# CF_DAC_FILTER.net
KiCad netlist of a schematic drawn in Altium Designer
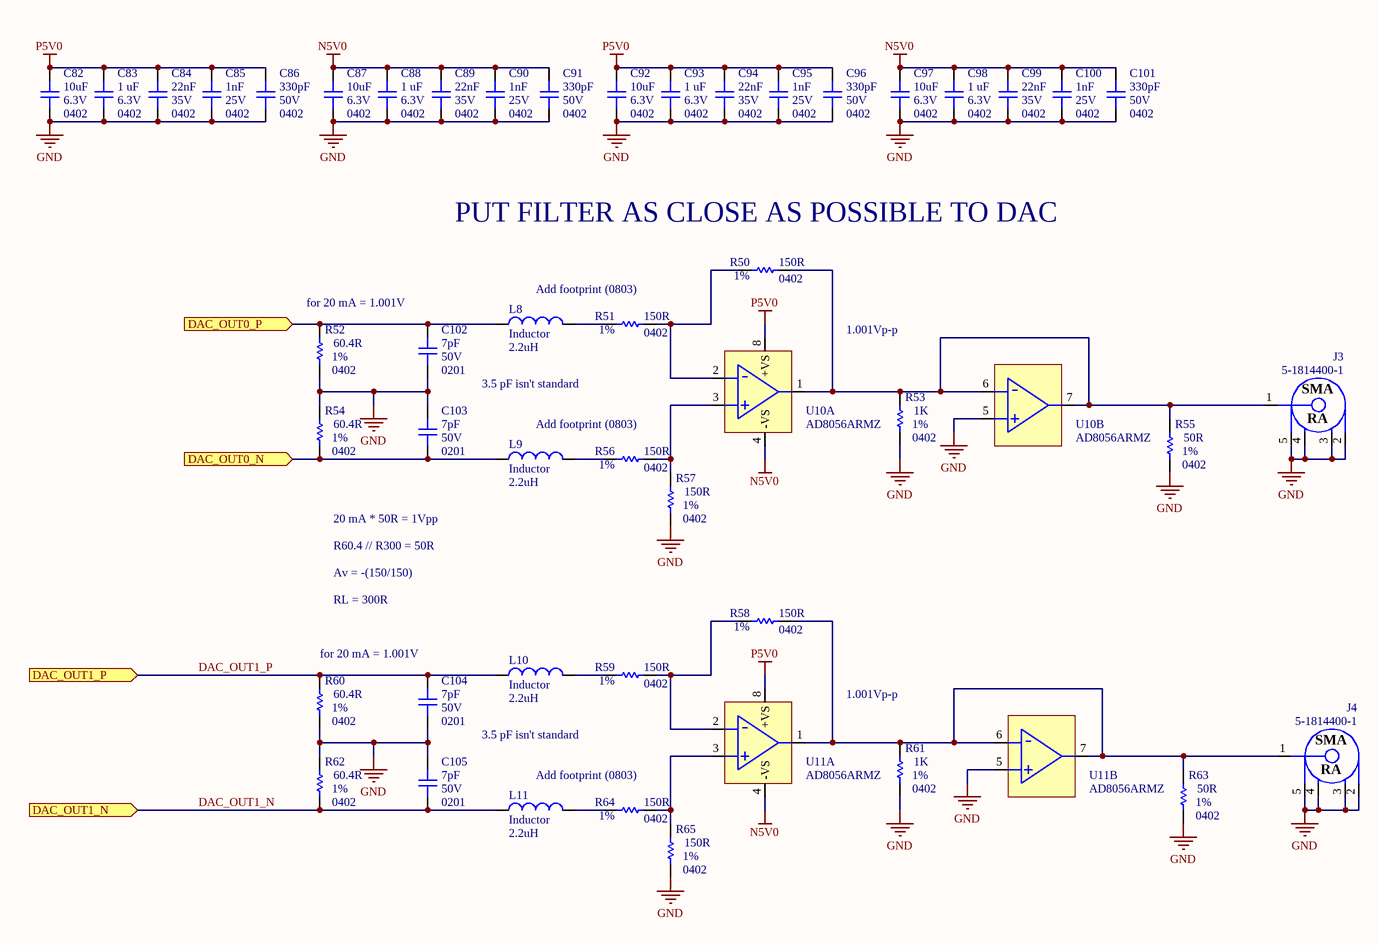
[diagram p0: CF_DAC_FILTER.SchDoc]

(export (version "E")
  (design (tool "Eeschema 10.0.6"))
  (components
    (comp (ref "C82")
      (value "10uF")
      (footprint "CAP_0402")
      (description "CAP - 0402")
      (fields
        (field (name "VOLTAGE") "6.3V")
        (field (name "PACKAGE") "0402")
        (field (name "CREATEDBY") "Jonathan Bouchard")
      )
      (libsource (lib "S7CAS_Lib2019_REV1_00") (part "CAP - 0402"))
    )
    (comp (ref "C83")
      (value "1 uF")
      (footprint "CAP_0402")
      (description "CAP - 0402")
      (fields
        (field (name "VOLTAGE") "6.3V")
        (field (name "PACKAGE") "0402")
        (field (name "CREATEDBY") "Jonathan Bouchard")
      )
      (libsource (lib "S7CAS_Lib2019_REV1_00") (part "CAP - 0402"))
    )
    (comp (ref "C84")
      (value "22nF")
      (footprint "CAP_0402")
      (description "CAP - 0402")
      (fields
        (field (name "VOLTAGE") "35V")
        (field (name "PACKAGE") "0402")
        (field (name "CREATEDBY") "Jonathan Bouchard")
      )
      (libsource (lib "S7CAS_Lib2019_REV1_00") (part "CAP - 0402"))
    )
    (comp (ref "C85")
      (value "1nF")
      (footprint "CAP_0402")
      (description "CAP - 0402")
      (fields
        (field (name "VOLTAGE") "25V")
        (field (name "PACKAGE") "0402")
        (field (name "CREATEDBY") "Jonathan Bouchard")
      )
      (libsource (lib "S7CAS_Lib2019_REV1_00") (part "CAP - 0402"))
    )
    (comp (ref "C86")
      (value "330pF")
      (footprint "CAP_0402")
      (description "CAP - 0402")
      (fields
        (field (name "VOLTAGE") "50V")
        (field (name "PACKAGE") "0402")
        (field (name "CREATEDBY") "Jonathan Bouchard")
      )
      (libsource (lib "S7CAS_Lib2019_REV1_00") (part "CAP - 0402"))
    )
    (comp (ref "C87")
      (value "10uF")
      (footprint "CAP_0402")
      (description "CAP - 0402")
      (fields
        (field (name "VOLTAGE") "6.3V")
        (field (name "PACKAGE") "0402")
        (field (name "CREATEDBY") "Jonathan Bouchard")
      )
      (libsource (lib "S7CAS_Lib2019_REV1_00") (part "CAP - 0402"))
    )
    (comp (ref "C88")
      (value "1 uF")
      (footprint "CAP_0402")
      (description "CAP - 0402")
      (fields
        (field (name "VOLTAGE") "6.3V")
        (field (name "PACKAGE") "0402")
        (field (name "CREATEDBY") "Jonathan Bouchard")
      )
      (libsource (lib "S7CAS_Lib2019_REV1_00") (part "CAP - 0402"))
    )
    (comp (ref "C89")
      (value "22nF")
      (footprint "CAP_0402")
      (description "CAP - 0402")
      (fields
        (field (name "VOLTAGE") "35V")
        (field (name "PACKAGE") "0402")
        (field (name "CREATEDBY") "Jonathan Bouchard")
      )
      (libsource (lib "S7CAS_Lib2019_REV1_00") (part "CAP - 0402"))
    )
    (comp (ref "C90")
      (value "1nF")
      (footprint "CAP_0402")
      (description "CAP - 0402")
      (fields
        (field (name "VOLTAGE") "25V")
        (field (name "PACKAGE") "0402")
        (field (name "CREATEDBY") "Jonathan Bouchard")
      )
      (libsource (lib "S7CAS_Lib2019_REV1_00") (part "CAP - 0402"))
    )
    (comp (ref "C91")
      (value "330pF")
      (footprint "CAP_0402")
      (description "CAP - 0402")
      (fields
        (field (name "VOLTAGE") "50V")
        (field (name "PACKAGE") "0402")
        (field (name "CREATEDBY") "Jonathan Bouchard")
      )
      (libsource (lib "S7CAS_Lib2019_REV1_00") (part "CAP - 0402"))
    )
    (comp (ref "C92")
      (value "10uF")
      (footprint "CAP_0402")
      (description "CAP - 0402")
      (fields
        (field (name "VOLTAGE") "6.3V")
        (field (name "PACKAGE") "0402")
        (field (name "CREATEDBY") "Jonathan Bouchard")
      )
      (libsource (lib "S7CAS_Lib2019_REV1_00") (part "CAP - 0402"))
    )
    (comp (ref "C93")
      (value "1 uF")
      (footprint "CAP_0402")
      (description "CAP - 0402")
      (fields
        (field (name "VOLTAGE") "6.3V")
        (field (name "PACKAGE") "0402")
        (field (name "CREATEDBY") "Jonathan Bouchard")
      )
      (libsource (lib "S7CAS_Lib2019_REV1_00") (part "CAP - 0402"))
    )
    (comp (ref "C94")
      (value "22nF")
      (footprint "CAP_0402")
      (description "CAP - 0402")
      (fields
        (field (name "VOLTAGE") "35V")
        (field (name "PACKAGE") "0402")
        (field (name "CREATEDBY") "Jonathan Bouchard")
      )
      (libsource (lib "S7CAS_Lib2019_REV1_00") (part "CAP - 0402"))
    )
    (comp (ref "C95")
      (value "1nF")
      (footprint "CAP_0402")
      (description "CAP - 0402")
      (fields
        (field (name "VOLTAGE") "25V")
        (field (name "PACKAGE") "0402")
        (field (name "CREATEDBY") "Jonathan Bouchard")
      )
      (libsource (lib "S7CAS_Lib2019_REV1_00") (part "CAP - 0402"))
    )
    (comp (ref "C96")
      (value "330pF")
      (footprint "CAP_0402")
      (description "CAP - 0402")
      (fields
        (field (name "VOLTAGE") "50V")
        (field (name "PACKAGE") "0402")
        (field (name "CREATEDBY") "Jonathan Bouchard")
      )
      (libsource (lib "S7CAS_Lib2019_REV1_00") (part "CAP - 0402"))
    )
    (comp (ref "C97")
      (value "10uF")
      (footprint "CAP_0402")
      (description "CAP - 0402")
      (fields
        (field (name "VOLTAGE") "6.3V")
        (field (name "PACKAGE") "0402")
        (field (name "CREATEDBY") "Jonathan Bouchard")
      )
      (libsource (lib "S7CAS_Lib2019_REV1_00") (part "CAP - 0402"))
    )
    (comp (ref "C98")
      (value "1 uF")
      (footprint "CAP_0402")
      (description "CAP - 0402")
      (fields
        (field (name "VOLTAGE") "6.3V")
        (field (name "PACKAGE") "0402")
        (field (name "CREATEDBY") "Jonathan Bouchard")
      )
      (libsource (lib "S7CAS_Lib2019_REV1_00") (part "CAP - 0402"))
    )
    (comp (ref "C99")
      (value "22nF")
      (footprint "CAP_0402")
      (description "CAP - 0402")
      (fields
        (field (name "VOLTAGE") "35V")
        (field (name "PACKAGE") "0402")
        (field (name "CREATEDBY") "Jonathan Bouchard")
      )
      (libsource (lib "S7CAS_Lib2019_REV1_00") (part "CAP - 0402"))
    )
    (comp (ref "C100")
      (value "1nF")
      (footprint "CAP_0402")
      (description "CAP - 0402")
      (fields
        (field (name "VOLTAGE") "25V")
        (field (name "PACKAGE") "0402")
        (field (name "CREATEDBY") "Jonathan Bouchard")
      )
      (libsource (lib "S7CAS_Lib2019_REV1_00") (part "CAP - 0402"))
    )
    (comp (ref "C101")
      (value "330pF")
      (footprint "CAP_0402")
      (description "CAP - 0402")
      (fields
        (field (name "VOLTAGE") "50V")
        (field (name "PACKAGE") "0402")
        (field (name "CREATEDBY") "Jonathan Bouchard")
      )
      (libsource (lib "S7CAS_Lib2019_REV1_00") (part "CAP - 0402"))
    )
    (comp (ref "C102")
      (value "7pF")
      (footprint "CAP_0201")
      (description "CAP - 0201")
      (fields
        (field (name "VOLTAGE") "50V")
        (field (name "PACKAGE") "0201")
        (field (name "CREATEDBY") "Jonathan Bouchard")
      )
      (libsource (lib "S7CAS_Lib2019_REV1_00") (part "CAP - 0201"))
    )
    (comp (ref "C103")
      (value "7pF")
      (footprint "CAP_0201")
      (description "CAP - 0201")
      (fields
        (field (name "VOLTAGE") "50V")
        (field (name "PACKAGE") "0201")
        (field (name "CREATEDBY") "Jonathan Bouchard")
      )
      (libsource (lib "S7CAS_Lib2019_REV1_00") (part "CAP - 0201"))
    )
    (comp (ref "C104")
      (value "7pF")
      (footprint "CAP_0201")
      (description "CAP - 0201")
      (fields
        (field (name "VOLTAGE") "50V")
        (field (name "PACKAGE") "0201")
        (field (name "CREATEDBY") "Jonathan Bouchard")
      )
      (libsource (lib "S7CAS_Lib2019_REV1_00") (part "CAP - 0201"))
    )
    (comp (ref "C105")
      (value "7pF")
      (footprint "CAP_0201")
      (description "CAP - 0201")
      (fields
        (field (name "VOLTAGE") "50V")
        (field (name "PACKAGE") "0201")
        (field (name "CREATEDBY") "Jonathan Bouchard")
      )
      (libsource (lib "S7CAS_Lib2019_REV1_00") (part "CAP - 0201"))
    )
    (comp (ref "J3")
      (value "5-1814400-1")
      (footprint "CONN_SMA_5-1814400-1")
      (description "CONN -  SMA JACK R/A 50 OHM - TH")
      (fields
        (field (name "MFG") "TE Connectivity AMP Connectors")
        (field (name "CREATEDBY") "Jonathan Bouchard")
      )
      (libsource (lib "S7CAS_Lib2019_REV1_00") (part "CONN_SMA_5-1814400-1"))
    )
    (comp (ref "J4")
      (value "5-1814400-1")
      (footprint "CONN_SMA_5-1814400-1")
      (description "CONN -  SMA JACK R/A 50 OHM - TH")
      (fields
        (field (name "MFG") "TE Connectivity AMP Connectors")
        (field (name "CREATEDBY") "Jonathan Bouchard")
      )
      (libsource (lib "S7CAS_Lib2019_REV1_00") (part "CONN_SMA_5-1814400-1"))
    )
    (comp (ref "L8")
      (value "Inductor")
      (footprint "0402-A")
      (fields (field (name "ALTIUM_VALUE") "2.2uH") (field (name "PUBLISHER") "Altium Limited"))
      (libsource (lib "Miscellaneous Devices") (part "Inductor"))
    )
    (comp (ref "L9")
      (value "Inductor")
      (footprint "0402-A")
      (fields (field (name "ALTIUM_VALUE") "2.2uH") (field (name "PUBLISHER") "Altium Limited"))
      (libsource (lib "Miscellaneous Devices") (part "Inductor"))
    )
    (comp (ref "L10")
      (value "Inductor")
      (footprint "0402-A")
      (fields (field (name "ALTIUM_VALUE") "2.2uH") (field (name "PUBLISHER") "Altium Limited"))
      (libsource (lib "Miscellaneous Devices") (part "Inductor"))
    )
    (comp (ref "L11")
      (value "Inductor")
      (footprint "0402-A")
      (fields (field (name "ALTIUM_VALUE") "2.2uH") (field (name "PUBLISHER") "Altium Limited"))
      (libsource (lib "Miscellaneous Devices") (part "Inductor"))
    )
    (comp (ref "R50")
      (value "150R")
      (footprint "RES_0402")
      (description "RES - 0402")
      (fields
        (field (name "VOLTAGE") "50V")
        (field (name "POWER") "1/16W")
        (field (name "PACKAGE") "0402")
        (field (name "PRECISION") "1%")
        (field (name "CREATEDBY") "Jonathan Bouchard")
      )
      (libsource (lib "S7CAS_Lib2019_REV1_00") (part "RES - 0402"))
    )
    (comp (ref "R51")
      (value "150R")
      (footprint "RES_0402")
      (description "RES - 0402")
      (fields
        (field (name "VOLTAGE") "50V")
        (field (name "POWER") "1/16W")
        (field (name "PACKAGE") "0402")
        (field (name "PRECISION") "1%")
        (field (name "CREATEDBY") "Jonathan Bouchard")
      )
      (libsource (lib "S7CAS_Lib2019_REV1_00") (part "RES - 0402"))
    )
    (comp (ref "R52")
      (value "60.4R")
      (footprint "RES_0402")
      (description "RES - 0402")
      (fields
        (field (name "VOLTAGE") "50V")
        (field (name "POWER") "1/16W")
        (field (name "PACKAGE") "0402")
        (field (name "PRECISION") "1%")
        (field (name "CREATEDBY") "Jonathan Bouchard")
      )
      (libsource (lib "S7CAS_Lib2019_REV1_00") (part "RES - 0402"))
    )
    (comp (ref "R53")
      (value "1K")
      (footprint "RES_0402")
      (description "RES - 0402")
      (fields
        (field (name "VOLTAGE") "50V")
        (field (name "POWER") "1/16W")
        (field (name "PACKAGE") "0402")
        (field (name "PRECISION") "1%")
        (field (name "CREATEDBY") "Jonathan Bouchard")
      )
      (libsource (lib "S7CAS_Lib2019_REV1_00") (part "RES - 0402"))
    )
    (comp (ref "R54")
      (value "60.4R")
      (footprint "RES_0402")
      (description "RES - 0402")
      (fields
        (field (name "VOLTAGE") "50V")
        (field (name "POWER") "1/16W")
        (field (name "PACKAGE") "0402")
        (field (name "PRECISION") "1%")
        (field (name "CREATEDBY") "Jonathan Bouchard")
      )
      (libsource (lib "S7CAS_Lib2019_REV1_00") (part "RES - 0402"))
    )
    (comp (ref "R55")
      (value "50R")
      (footprint "RES_0402")
      (description "RES - 0402")
      (fields
        (field (name "VOLTAGE") "50V")
        (field (name "POWER") "1/16W")
        (field (name "PACKAGE") "0402")
        (field (name "PRECISION") "1%")
        (field (name "CREATEDBY") "Jonathan Bouchard")
      )
      (libsource (lib "S7CAS_Lib2019_REV1_00") (part "RES - 0402"))
    )
    (comp (ref "R56")
      (value "150R")
      (footprint "RES_0402")
      (description "RES - 0402")
      (fields
        (field (name "VOLTAGE") "50V")
        (field (name "POWER") "1/16W")
        (field (name "PACKAGE") "0402")
        (field (name "PRECISION") "1%")
        (field (name "CREATEDBY") "Jonathan Bouchard")
      )
      (libsource (lib "S7CAS_Lib2019_REV1_00") (part "RES - 0402"))
    )
    (comp (ref "R57")
      (value "150R")
      (footprint "RES_0402")
      (description "RES - 0402")
      (fields
        (field (name "VOLTAGE") "50V")
        (field (name "POWER") "1/16W")
        (field (name "PACKAGE") "0402")
        (field (name "PRECISION") "1%")
        (field (name "CREATEDBY") "Jonathan Bouchard")
      )
      (libsource (lib "S7CAS_Lib2019_REV1_00") (part "RES - 0402"))
    )
    (comp (ref "R58")
      (value "150R")
      (footprint "RES_0402")
      (description "RES - 0402")
      (fields
        (field (name "VOLTAGE") "50V")
        (field (name "POWER") "1/16W")
        (field (name "PACKAGE") "0402")
        (field (name "PRECISION") "1%")
        (field (name "CREATEDBY") "Jonathan Bouchard")
      )
      (libsource (lib "S7CAS_Lib2019_REV1_00") (part "RES - 0402"))
    )
    (comp (ref "R59")
      (value "150R")
      (footprint "RES_0402")
      (description "RES - 0402")
      (fields
        (field (name "VOLTAGE") "50V")
        (field (name "POWER") "1/16W")
        (field (name "PACKAGE") "0402")
        (field (name "PRECISION") "1%")
        (field (name "CREATEDBY") "Jonathan Bouchard")
      )
      (libsource (lib "S7CAS_Lib2019_REV1_00") (part "RES - 0402"))
    )
    (comp (ref "R60")
      (value "60.4R")
      (footprint "RES_0402")
      (description "RES - 0402")
      (fields
        (field (name "VOLTAGE") "50V")
        (field (name "POWER") "1/16W")
        (field (name "PACKAGE") "0402")
        (field (name "PRECISION") "1%")
        (field (name "CREATEDBY") "Jonathan Bouchard")
      )
      (libsource (lib "S7CAS_Lib2019_REV1_00") (part "RES - 0402"))
    )
    (comp (ref "R61")
      (value "1K")
      (footprint "RES_0402")
      (description "RES - 0402")
      (fields
        (field (name "VOLTAGE") "50V")
        (field (name "POWER") "1/16W")
        (field (name "PACKAGE") "0402")
        (field (name "PRECISION") "1%")
        (field (name "CREATEDBY") "Jonathan Bouchard")
      )
      (libsource (lib "S7CAS_Lib2019_REV1_00") (part "RES - 0402"))
    )
    (comp (ref "R62")
      (value "60.4R")
      (footprint "RES_0402")
      (description "RES - 0402")
      (fields
        (field (name "VOLTAGE") "50V")
        (field (name "POWER") "1/16W")
        (field (name "PACKAGE") "0402")
        (field (name "PRECISION") "1%")
        (field (name "CREATEDBY") "Jonathan Bouchard")
      )
      (libsource (lib "S7CAS_Lib2019_REV1_00") (part "RES - 0402"))
    )
    (comp (ref "R63")
      (value "50R")
      (footprint "RES_0402")
      (description "RES - 0402")
      (fields
        (field (name "VOLTAGE") "50V")
        (field (name "POWER") "1/16W")
        (field (name "PACKAGE") "0402")
        (field (name "PRECISION") "1%")
        (field (name "CREATEDBY") "Jonathan Bouchard")
      )
      (libsource (lib "S7CAS_Lib2019_REV1_00") (part "RES - 0402"))
    )
    (comp (ref "R64")
      (value "150R")
      (footprint "RES_0402")
      (description "RES - 0402")
      (fields
        (field (name "VOLTAGE") "50V")
        (field (name "POWER") "1/16W")
        (field (name "PACKAGE") "0402")
        (field (name "PRECISION") "1%")
        (field (name "CREATEDBY") "Jonathan Bouchard")
      )
      (libsource (lib "S7CAS_Lib2019_REV1_00") (part "RES - 0402"))
    )
    (comp (ref "R65")
      (value "150R")
      (footprint "RES_0402")
      (description "RES - 0402")
      (fields
        (field (name "VOLTAGE") "50V")
        (field (name "POWER") "1/16W")
        (field (name "PACKAGE") "0402")
        (field (name "PRECISION") "1%")
        (field (name "CREATEDBY") "Jonathan Bouchard")
      )
      (libsource (lib "S7CAS_Lib2019_REV1_00") (part "RES - 0402"))
    )
    (comp (ref "U10")
      (value "AD8056ARMZ")
      (footprint "OPAMP_AD8056ARMZ")
      (description "OPAMP - VFB 300MHZ - 8MSOP")
      (fields
        (field (name "VOLTAGE") "8 V ~ 12 V, ±4 V ~ 6 V")
        (field (name "MFG") "Analog Devices")
        (field (name "CREATEDBY") "Jonathan Bouchard")
      )
      (libsource (lib "S7CAS_Lib2019_REV1_00") (part "OPAMP_AD8056ARMZ"))
    )
    (comp (ref "U11")
      (value "AD8056ARMZ")
      (footprint "OPAMP_AD8056ARMZ")
      (description "OPAMP - VFB 300MHZ - 8MSOP")
      (fields
        (field (name "VOLTAGE") "8 V ~ 12 V, ±4 V ~ 6 V")
        (field (name "MFG") "Analog Devices")
        (field (name "CREATEDBY") "Jonathan Bouchard")
      )
      (libsource (lib "S7CAS_Lib2019_REV1_00") (part "OPAMP_AD8056ARMZ"))
    )
  )
  (nets
    (net (code "1") (name "/DAC_OUT0_N") (class "Default")
      (node (ref "C103") (pin "1") (pinfunction "1_1") (pintype "passive"))
      (node (ref "L9") (pin "1") (pinfunction "1_1") (pintype "passive"))
      (node (ref "R54") (pin "1") (pinfunction "1_1") (pintype "passive"))
    )
    (net (code "2") (name "/DAC_OUT0_P") (class "Default")
      (node (ref "C102") (pin "2") (pinfunction "2_2") (pintype "passive"))
      (node (ref "L8") (pin "1") (pinfunction "1_1") (pintype "passive"))
      (node (ref "R52") (pin "2") (pinfunction "2_2") (pintype "passive"))
    )
    (net (code "3") (name "/DAC_OUT1_N") (class "Default")
      (node (ref "C105") (pin "1") (pinfunction "1_1") (pintype "passive"))
      (node (ref "L11") (pin "1") (pinfunction "1_1") (pintype "passive"))
      (node (ref "R62") (pin "1") (pinfunction "1_1") (pintype "passive"))
    )
    (net (code "4") (name "/DAC_OUT1_P") (class "Default")
      (node (ref "C104") (pin "2") (pinfunction "2_2") (pintype "passive"))
      (node (ref "L10") (pin "1") (pinfunction "1_1") (pintype "passive"))
      (node (ref "R60") (pin "2") (pinfunction "2_2") (pintype "passive"))
    )
    (net (code "5") (name "GND") (class "Default")
      (node (ref "C100") (pin "1") (pinfunction "1_1") (pintype "passive"))
      (node (ref "C101") (pin "1") (pinfunction "1_1") (pintype "passive"))
      (node (ref "C102") (pin "1") (pinfunction "1_1") (pintype "passive"))
      (node (ref "C103") (pin "2") (pinfunction "2_2") (pintype "passive"))
      (node (ref "C104") (pin "1") (pinfunction "1_1") (pintype "passive"))
      (node (ref "C105") (pin "2") (pinfunction "2_2") (pintype "passive"))
      (node (ref "C82") (pin "1") (pinfunction "1_1") (pintype "passive"))
      (node (ref "C83") (pin "1") (pinfunction "1_1") (pintype "passive"))
      (node (ref "C84") (pin "1") (pinfunction "1_1") (pintype "passive"))
      (node (ref "C85") (pin "1") (pinfunction "1_1") (pintype "passive"))
      (node (ref "C86") (pin "1") (pinfunction "1_1") (pintype "passive"))
      (node (ref "C87") (pin "1") (pinfunction "1_1") (pintype "passive"))
      (node (ref "C88") (pin "1") (pinfunction "1_1") (pintype "passive"))
      (node (ref "C89") (pin "1") (pinfunction "1_1") (pintype "passive"))
      (node (ref "C90") (pin "1") (pinfunction "1_1") (pintype "passive"))
      (node (ref "C91") (pin "1") (pinfunction "1_1") (pintype "passive"))
      (node (ref "C92") (pin "1") (pinfunction "1_1") (pintype "passive"))
      (node (ref "C93") (pin "1") (pinfunction "1_1") (pintype "passive"))
      (node (ref "C94") (pin "1") (pinfunction "1_1") (pintype "passive"))
      (node (ref "C95") (pin "1") (pinfunction "1_1") (pintype "passive"))
      (node (ref "C96") (pin "1") (pinfunction "1_1") (pintype "passive"))
      (node (ref "C97") (pin "1") (pinfunction "1_1") (pintype "passive"))
      (node (ref "C98") (pin "1") (pinfunction "1_1") (pintype "passive"))
      (node (ref "C99") (pin "1") (pinfunction "1_1") (pintype "passive"))
      (node (ref "J3") (pin "2") (pinfunction "2_2") (pintype "passive"))
      (node (ref "J3") (pin "3") (pinfunction "3_3") (pintype "passive"))
      (node (ref "J3") (pin "4") (pinfunction "4_4") (pintype "passive"))
      (node (ref "J3") (pin "5") (pinfunction "5_5") (pintype "passive"))
      (node (ref "J4") (pin "2") (pinfunction "2_2") (pintype "passive"))
      (node (ref "J4") (pin "3") (pinfunction "3_3") (pintype "passive"))
      (node (ref "J4") (pin "4") (pinfunction "4_4") (pintype "passive"))
      (node (ref "J4") (pin "5") (pinfunction "5_5") (pintype "passive"))
      (node (ref "R52") (pin "1") (pinfunction "1_1") (pintype "passive"))
      (node (ref "R53") (pin "1") (pinfunction "1_1") (pintype "passive"))
      (node (ref "R54") (pin "2") (pinfunction "2_2") (pintype "passive"))
      (node (ref "R55") (pin "1") (pinfunction "1_1") (pintype "passive"))
      (node (ref "R57") (pin "1") (pinfunction "1_1") (pintype "passive"))
      (node (ref "R60") (pin "1") (pinfunction "1_1") (pintype "passive"))
      (node (ref "R61") (pin "1") (pinfunction "1_1") (pintype "passive"))
      (node (ref "R62") (pin "2") (pinfunction "2_2") (pintype "passive"))
      (node (ref "R63") (pin "1") (pinfunction "1_1") (pintype "passive"))
      (node (ref "R65") (pin "1") (pinfunction "1_1") (pintype "passive"))
      (node (ref "U10") (pin "5") (pinfunction "+IN2_5") (pintype "passive"))
      (node (ref "U11") (pin "5") (pinfunction "+IN2_5") (pintype "passive"))
    )
    (net (code "6") (name "N5V0") (class "Default")
      (node (ref "C100") (pin "2") (pinfunction "2_2") (pintype "passive"))
      (node (ref "C101") (pin "2") (pinfunction "2_2") (pintype "passive"))
      (node (ref "C87") (pin "2") (pinfunction "2_2") (pintype "passive"))
      (node (ref "C88") (pin "2") (pinfunction "2_2") (pintype "passive"))
      (node (ref "C89") (pin "2") (pinfunction "2_2") (pintype "passive"))
      (node (ref "C90") (pin "2") (pinfunction "2_2") (pintype "passive"))
      (node (ref "C91") (pin "2") (pinfunction "2_2") (pintype "passive"))
      (node (ref "C97") (pin "2") (pinfunction "2_2") (pintype "passive"))
      (node (ref "C98") (pin "2") (pinfunction "2_2") (pintype "passive"))
      (node (ref "C99") (pin "2") (pinfunction "2_2") (pintype "passive"))
      (node (ref "U10") (pin "4") (pinfunction "-VS_4") (pintype "passive"))
      (node (ref "U11") (pin "4") (pinfunction "-VS_4") (pintype "passive"))
    )
    (net (code "7") (name "Net-(L8-Pad2)") (class "Default")
      (node (ref "L8") (pin "2") (pinfunction "2_2") (pintype "passive"))
      (node (ref "R51") (pin "2") (pinfunction "2_2") (pintype "passive"))
    )
    (net (code "8") (name "Net-(L9-Pad2)") (class "Default")
      (node (ref "L9") (pin "2") (pinfunction "2_2") (pintype "passive"))
      (node (ref "R56") (pin "2") (pinfunction "2_2") (pintype "passive"))
    )
    (net (code "9") (name "Net-(L10-Pad2)") (class "Default")
      (node (ref "L10") (pin "2") (pinfunction "2_2") (pintype "passive"))
      (node (ref "R59") (pin "2") (pinfunction "2_2") (pintype "passive"))
    )
    (net (code "10") (name "Net-(L11-Pad2)") (class "Default")
      (node (ref "L11") (pin "2") (pinfunction "2_2") (pintype "passive"))
      (node (ref "R64") (pin "2") (pinfunction "2_2") (pintype "passive"))
    )
    (net (code "11") (name "Net-(U10A-+IN1)") (class "Default")
      (node (ref "R56") (pin "1") (pinfunction "1_1") (pintype "passive"))
      (node (ref "R57") (pin "2") (pinfunction "2_2") (pintype "passive"))
      (node (ref "U10") (pin "3") (pinfunction "+IN1_3") (pintype "passive"))
    )
    (net (code "12") (name "Net-(U10A--IN1)") (class "Default")
      (node (ref "R50") (pin "2") (pinfunction "2_2") (pintype "passive"))
      (node (ref "R51") (pin "1") (pinfunction "1_1") (pintype "passive"))
      (node (ref "U10") (pin "2") (pinfunction "-IN1_2") (pintype "passive"))
    )
    (net (code "13") (name "Net-(U10A-OUT1)") (class "Default")
      (node (ref "J3") (pin "1") (pinfunction "1_1") (pintype "passive"))
      (node (ref "R50") (pin "1") (pinfunction "1_1") (pintype "passive"))
      (node (ref "R53") (pin "2") (pinfunction "2_2") (pintype "passive"))
      (node (ref "R55") (pin "2") (pinfunction "2_2") (pintype "passive"))
      (node (ref "U10") (pin "1") (pinfunction "OUT1_1") (pintype "passive"))
      (node (ref "U10") (pin "6") (pinfunction "-IN2_6") (pintype "passive"))
      (node (ref "U10") (pin "7") (pinfunction "OUT2_7") (pintype "passive"))
    )
    (net (code "14") (name "Net-(U11A-+IN1)") (class "Default")
      (node (ref "R64") (pin "1") (pinfunction "1_1") (pintype "passive"))
      (node (ref "R65") (pin "2") (pinfunction "2_2") (pintype "passive"))
      (node (ref "U11") (pin "3") (pinfunction "+IN1_3") (pintype "passive"))
    )
    (net (code "15") (name "Net-(U11A--IN1)") (class "Default")
      (node (ref "R58") (pin "2") (pinfunction "2_2") (pintype "passive"))
      (node (ref "R59") (pin "1") (pinfunction "1_1") (pintype "passive"))
      (node (ref "U11") (pin "2") (pinfunction "-IN1_2") (pintype "passive"))
    )
    (net (code "16") (name "Net-(U11A-OUT1)") (class "Default")
      (node (ref "J4") (pin "1") (pinfunction "1_1") (pintype "passive"))
      (node (ref "R58") (pin "1") (pinfunction "1_1") (pintype "passive"))
      (node (ref "R61") (pin "2") (pinfunction "2_2") (pintype "passive"))
      (node (ref "R63") (pin "2") (pinfunction "2_2") (pintype "passive"))
      (node (ref "U11") (pin "1") (pinfunction "OUT1_1") (pintype "passive"))
      (node (ref "U11") (pin "6") (pinfunction "-IN2_6") (pintype "passive"))
      (node (ref "U11") (pin "7") (pinfunction "OUT2_7") (pintype "passive"))
    )
    (net (code "17") (name "P5V0") (class "Default")
      (node (ref "C82") (pin "2") (pinfunction "2_2") (pintype "passive"))
      (node (ref "C83") (pin "2") (pinfunction "2_2") (pintype "passive"))
      (node (ref "C84") (pin "2") (pinfunction "2_2") (pintype "passive"))
      (node (ref "C85") (pin "2") (pinfunction "2_2") (pintype "passive"))
      (node (ref "C86") (pin "2") (pinfunction "2_2") (pintype "passive"))
      (node (ref "C92") (pin "2") (pinfunction "2_2") (pintype "passive"))
      (node (ref "C93") (pin "2") (pinfunction "2_2") (pintype "passive"))
      (node (ref "C94") (pin "2") (pinfunction "2_2") (pintype "passive"))
      (node (ref "C95") (pin "2") (pinfunction "2_2") (pintype "passive"))
      (node (ref "C96") (pin "2") (pinfunction "2_2") (pintype "passive"))
      (node (ref "U10") (pin "8") (pinfunction "+VS_8") (pintype "passive"))
      (node (ref "U11") (pin "8") (pinfunction "+VS_8") (pintype "passive"))
    )
  )
)
